# arm-debugger.net
KiCad netlist of a schematic drawn in Altium Designer
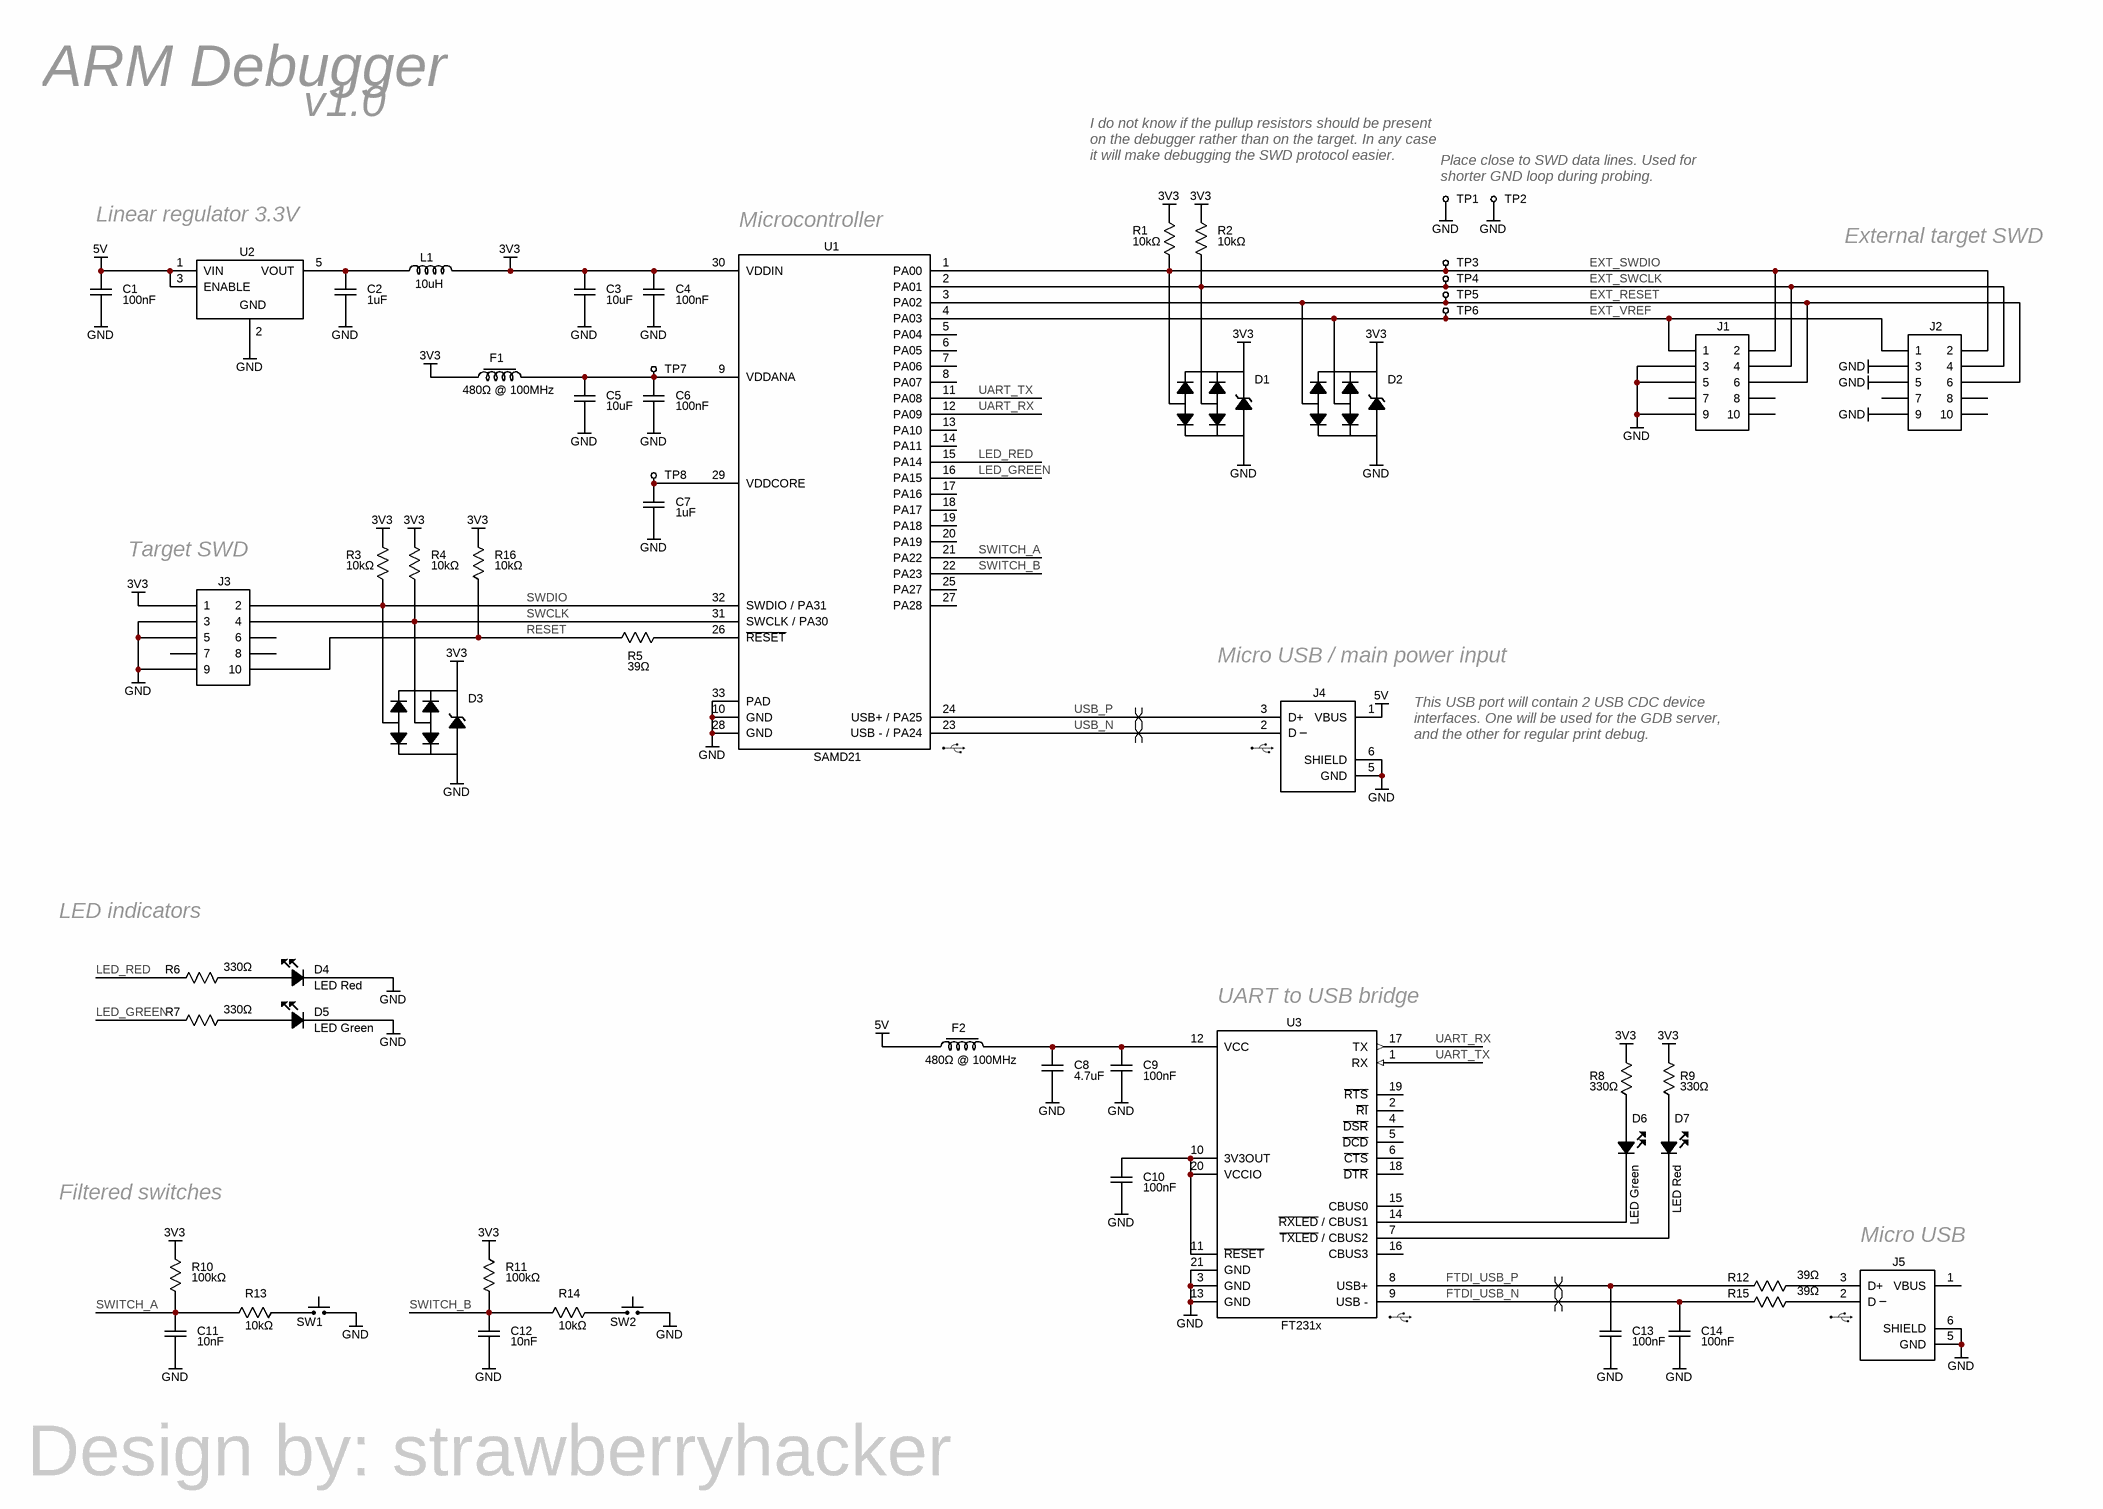
[diagram p0: arm-debugger.SchDoc]

(export (version "E")
  (design (tool "Eeschema 10.0.6"))
  (components
    (comp (ref "C1")
      (value "100nF")
      (footprint "capacitor 0603")
      (description "Capacitor 0603")
      (fields (field (name "Comment") "passive_5"))
      (libsource (lib "passive") (part "passive_5"))
    )
    (comp (ref "C2")
      (value "1uF")
      (footprint "capacitor 0603")
      (description "Capacitor 0603")
      (fields (field (name "Comment") "passive_5"))
      (libsource (lib "passive") (part "passive_5"))
    )
    (comp (ref "C3")
      (value "10uF")
      (footprint "capacitor 0603")
      (description "Capacitor 0603")
      (fields (field (name "Comment") "passive_5"))
      (libsource (lib "passive") (part "passive_5"))
    )
    (comp (ref "C4")
      (value "100nF")
      (footprint "capacitor 0603")
      (description "Capacitor 0603")
      (fields (field (name "Comment") "passive_5"))
      (libsource (lib "passive") (part "passive_5"))
    )
    (comp (ref "C5")
      (value "10uF")
      (footprint "capacitor 0603")
      (description "Capacitor 0603")
      (fields (field (name "Comment") "passive_5"))
      (libsource (lib "passive") (part "passive_5"))
    )
    (comp (ref "C6")
      (value "100nF")
      (footprint "capacitor 0603")
      (description "Capacitor 0603")
      (fields (field (name "Comment") "passive_5"))
      (libsource (lib "passive") (part "passive_5"))
    )
    (comp (ref "C7")
      (value "1uF")
      (footprint "capacitor 0603")
      (description "Capacitor 0603")
      (fields (field (name "Comment") "passive_5"))
      (libsource (lib "passive") (part "passive_5"))
    )
    (comp (ref "C8")
      (value "4.7uF")
      (footprint "capacitor 0603")
      (description "Capacitor 0603")
      (fields (field (name "Comment") "passive_5"))
      (libsource (lib "passive") (part "passive_5"))
    )
    (comp (ref "C9")
      (value "100nF")
      (footprint "capacitor 0603")
      (description "Capacitor 0603")
      (fields (field (name "Comment") "passive_5"))
      (libsource (lib "passive") (part "passive_5"))
    )
    (comp (ref "C10")
      (value "100nF")
      (footprint "capacitor 0603")
      (description "Capacitor 0603")
      (fields (field (name "Comment") "passive_5"))
      (libsource (lib "passive") (part "passive_5"))
    )
    (comp (ref "C11")
      (value "10nF")
      (footprint "capacitor 0603")
      (description "Capacitor 0603")
      (fields (field (name "Comment") "passive_5"))
      (libsource (lib "passive") (part "passive_5"))
    )
    (comp (ref "C12")
      (value "10nF")
      (footprint "capacitor 0603")
      (description "Capacitor 0603")
      (fields (field (name "Comment") "passive_5"))
      (libsource (lib "passive") (part "passive_5"))
    )
    (comp (ref "C13")
      (value "100nF")
      (footprint "capacitor 0603")
      (description "Capacitor 0603")
      (fields (field (name "Comment") "passive_5"))
      (libsource (lib "passive") (part "passive_5"))
    )
    (comp (ref "C14")
      (value "100nF")
      (footprint "capacitor 0603")
      (description "Capacitor 0603")
      (fields (field (name "Comment") "passive_5"))
      (libsource (lib "passive") (part "passive_5"))
    )
    (comp (ref "D1")
      (value "diode_3")
      (footprint "CM1293A-02SR")
      (description "TVS, 2 channels, standoff 3.3V,  diode array with avalanche diode")
      (libsource (lib "diode") (part "diode_3"))
    )
    (comp (ref "D2")
      (value "diode_3")
      (footprint "CM1293A-02SR")
      (description "TVS, 2 channels, standoff 3.3V,  diode array with avalanche diode")
      (libsource (lib "diode") (part "diode_3"))
    )
    (comp (ref "D3")
      (value "diode_3")
      (footprint "CM1293A-02SR")
      (description "TVS, 2 channels, standoff 3.3V,  diode array with avalanche diode")
      (libsource (lib "diode") (part "diode_3"))
    )
    (comp (ref "D4")
      (value "LED Red")
      (footprint "LED 0603 red")
      (description "LED 0603 red")
      (libsource (lib "diode") (part "diode_0"))
    )
    (comp (ref "D5")
      (value "LED Green")
      (footprint "LED 0603 green")
      (description "LED 0603 green")
      (libsource (lib "diode") (part "diode_1"))
    )
    (comp (ref "D6")
      (value "LED Green")
      (footprint "LED 0603 green")
      (description "LED 0603 green")
      (libsource (lib "diode") (part "diode_1"))
    )
    (comp (ref "D7")
      (value "LED Red")
      (footprint "LED 0603 red")
      (description "LED 0603 red")
      (libsource (lib "diode") (part "diode_0"))
    )
    (comp (ref "F1")
      (value "480Ω @ 100MHz")
      (footprint "ferrit bead 0603")
      (description "Ferrite bead 0603")
      (fields (field (name "Comment") "passive_8"))
      (libsource (lib "passive") (part "passive_8"))
    )
    (comp (ref "F2")
      (value "480Ω @ 100MHz")
      (footprint "ferrit bead 0603")
      (description "Ferrite bead 0603")
      (fields (field (name "Comment") "passive_8"))
      (libsource (lib "passive") (part "passive_8"))
    )
    (comp (ref "J1")
      (value "Header 1.27mm")
      (footprint "header male 2x5, pitch 1.27mm")
      (description "Header male 2x5, pitch 1.27mm")
      (libsource (lib "connector") (part "connector_17"))
    )
    (comp (ref "J2")
      (value "Header 2.54mm")
      (footprint "header male 2x5, pitch 2.54mm")
      (description "Header male 2x5, pitch 2.54mm")
      (libsource (lib "connector") (part "connector_30"))
    )
    (comp (ref "J3")
      (value "Header 1.27mm")
      (footprint "header male 2x5, pitch 1.27mm")
      (description "Header male 2x5, pitch 1.27mm")
      (libsource (lib "connector") (part "connector_17"))
    )
    (comp (ref "J4")
      (value "USB micro B")
      (footprint "USB mico B female")
      (libsource (lib "connector") (part "connector_34"))
    )
    (comp (ref "J5")
      (value "USB micro B")
      (footprint "USB mico B female")
      (libsource (lib "connector") (part "connector_34"))
    )
    (comp (ref "L1")
      (value "10uH")
      (footprint "inductor 0603")
      (description "Inductor 0603")
      (fields (field (name "Comment") "passive_9"))
      (libsource (lib "passive") (part "passive_9"))
    )
    (comp (ref "R1")
      (value "10kΩ")
      (footprint "resistor 0603")
      (description "Resistor 0603")
      (fields (field (name "Comment") "passive_2"))
      (libsource (lib "passive") (part "passive_2"))
    )
    (comp (ref "R2")
      (value "10kΩ")
      (footprint "resistor 0603")
      (description "Resistor 0603")
      (fields (field (name "Comment") "passive_2"))
      (libsource (lib "passive") (part "passive_2"))
    )
    (comp (ref "R3")
      (value "10kΩ")
      (footprint "resistor 0603")
      (description "Resistor 0603")
      (fields (field (name "Comment") "passive_2"))
      (libsource (lib "passive") (part "passive_2"))
    )
    (comp (ref "R4")
      (value "10kΩ")
      (footprint "resistor 0603")
      (description "Resistor 0603")
      (fields (field (name "Comment") "passive_2"))
      (libsource (lib "passive") (part "passive_2"))
    )
    (comp (ref "R5")
      (value "39Ω")
      (footprint "resistor 0603")
      (description "Resistor 0603")
      (fields (field (name "Comment") "passive_2"))
      (libsource (lib "passive") (part "passive_2"))
    )
    (comp (ref "R6")
      (value "330Ω")
      (footprint "resistor 0603")
      (description "Resistor 0603")
      (fields (field (name "Comment") "passive_2"))
      (libsource (lib "passive") (part "passive_2"))
    )
    (comp (ref "R7")
      (value "330Ω")
      (footprint "resistor 0603")
      (description "Resistor 0603")
      (fields (field (name "Comment") "passive_2"))
      (libsource (lib "passive") (part "passive_2"))
    )
    (comp (ref "R8")
      (value "330Ω")
      (footprint "resistor 0603")
      (description "Resistor 0603")
      (fields (field (name "Comment") "passive_2"))
      (libsource (lib "passive") (part "passive_2"))
    )
    (comp (ref "R9")
      (value "330Ω")
      (footprint "resistor 0603")
      (description "Resistor 0603")
      (fields (field (name "Comment") "passive_2"))
      (libsource (lib "passive") (part "passive_2"))
    )
    (comp (ref "R10")
      (value "100kΩ")
      (footprint "resistor 0603")
      (description "Resistor 0603")
      (fields (field (name "Comment") "passive_2"))
      (libsource (lib "passive") (part "passive_2"))
    )
    (comp (ref "R11")
      (value "100kΩ")
      (footprint "resistor 0603")
      (description "Resistor 0603")
      (fields (field (name "Comment") "passive_2"))
      (libsource (lib "passive") (part "passive_2"))
    )
    (comp (ref "R12")
      (value "39Ω")
      (footprint "resistor 0603")
      (description "Resistor 0603")
      (fields (field (name "Comment") "passive_2"))
      (libsource (lib "passive") (part "passive_2"))
    )
    (comp (ref "R13")
      (value "10kΩ")
      (footprint "resistor 0603")
      (description "Resistor 0603")
      (fields (field (name "Comment") "passive_2"))
      (libsource (lib "passive") (part "passive_2"))
    )
    (comp (ref "R14")
      (value "10kΩ")
      (footprint "resistor 0603")
      (description "Resistor 0603")
      (fields (field (name "Comment") "passive_2"))
      (libsource (lib "passive") (part "passive_2"))
    )
    (comp (ref "R15")
      (value "39Ω")
      (footprint "resistor 0603")
      (description "Resistor 0603")
      (fields (field (name "Comment") "passive_2"))
      (libsource (lib "passive") (part "passive_2"))
    )
    (comp (ref "R16")
      (value "10kΩ")
      (footprint "resistor 0603")
      (description "Resistor 0603")
      (fields (field (name "Comment") "passive_2"))
      (libsource (lib "passive") (part "passive_2"))
    )
    (comp (ref "SW1")
      (value "connector_35")
      (footprint "KMR621NG LFS")
      (description "Tactile switch SMD, tiny")
      (libsource (lib "sensor") (part "connector_35"))
    )
    (comp (ref "SW2")
      (value "connector_35")
      (footprint "KMR621NG LFS")
      (description "Tactile switch SMD, tiny")
      (libsource (lib "sensor") (part "connector_35"))
    )
    (comp (ref "TP1")
      (value "misc_2")
      (footprint "testpoint round, diameter 1mm")
      (description "Test-point round, diameter 1.0mm")
      (libsource (lib "miscellaneous") (part "misc_2"))
    )
    (comp (ref "TP2")
      (value "misc_2")
      (footprint "testpoint round, diameter 1mm")
      (description "Test-point round, diameter 1.0mm")
      (libsource (lib "miscellaneous") (part "misc_2"))
    )
    (comp (ref "TP3")
      (value "misc_2")
      (footprint "testpoint round, diameter 1mm")
      (description "Test-point round, diameter 1.0mm")
      (libsource (lib "miscellaneous") (part "misc_2"))
    )
    (comp (ref "TP4")
      (value "misc_2")
      (footprint "testpoint round, diameter 1mm")
      (description "Test-point round, diameter 1.0mm")
      (libsource (lib "miscellaneous") (part "misc_2"))
    )
    (comp (ref "TP5")
      (value "misc_2")
      (footprint "testpoint round, diameter 1mm")
      (description "Test-point round, diameter 1.0mm")
      (libsource (lib "miscellaneous") (part "misc_2"))
    )
    (comp (ref "TP6")
      (value "misc_2")
      (footprint "testpoint round, diameter 1mm")
      (description "Test-point round, diameter 1.0mm")
      (libsource (lib "miscellaneous") (part "misc_2"))
    )
    (comp (ref "TP7")
      (value "misc_2")
      (footprint "testpoint round, diameter 1mm")
      (description "Test-point round, diameter 1.0mm")
      (libsource (lib "miscellaneous") (part "misc_2"))
    )
    (comp (ref "TP8")
      (value "misc_2")
      (footprint "testpoint round, diameter 1mm")
      (description "Test-point round, diameter 1.0mm")
      (libsource (lib "miscellaneous") (part "misc_2"))
    )
    (comp (ref "U1")
      (value "SAMD21")
      (footprint "ATSAMD21E17D-MUT")
      (description "SAMD21, 48 MHz, 128KB flash, 16KB RAM, 32 pins, USB device")
      (libsource (lib "cpu") (part "cpu_0"))
    )
    (comp (ref "U2")
      (value "regulator_1")
      (footprint "TCR2EF33,LM(CT")
      (description "LDO fixed, 3.3V output, 0.2V dropout, 200mA")
      (libsource (lib "voltage-regulator") (part "regulator_1"))
    )
    (comp (ref "U3")
      (value "FT231x")
      (footprint "FT231XQ-R")
      (description "USB to UART converter, FTDI, single")
      (libsource (lib "integrated-circuit") (part "ic_1"))
    )
  )
  (nets
    (net (code "1") (name "/EXT_RESET") (class "Default")
      (node (ref "D2") (pin "2") (pintype "passive"))
      (node (ref "J1") (pin "6") (pinfunction "6_6") (pintype "passive"))
      (node (ref "J2") (pin "6") (pinfunction "6_6") (pintype "passive"))
      (node (ref "TP5") (pin "1") (pintype "passive"))
      (node (ref "U1") (pin "3") (pinfunction "PA02_3") (pintype "passive"))
    )
    (net (code "2") (name "/EXT_SWCLK") (class "Default")
      (node (ref "D1") (pin "3") (pintype "passive"))
      (node (ref "J1") (pin "4") (pinfunction "4_4") (pintype "passive"))
      (node (ref "J2") (pin "4") (pinfunction "4_4") (pintype "passive"))
      (node (ref "R2") (pin "1") (pintype "passive"))
      (node (ref "TP4") (pin "1") (pintype "passive"))
      (node (ref "U1") (pin "2") (pinfunction "PA01_2") (pintype "passive"))
    )
    (net (code "3") (name "/EXT_SWDIO") (class "Default")
      (node (ref "D1") (pin "2") (pintype "passive"))
      (node (ref "J1") (pin "2") (pinfunction "2_2") (pintype "passive"))
      (node (ref "J2") (pin "2") (pinfunction "2_2") (pintype "passive"))
      (node (ref "R1") (pin "1") (pintype "passive"))
      (node (ref "TP3") (pin "1") (pintype "passive"))
      (node (ref "U1") (pin "1") (pinfunction "PA00_1") (pintype "passive"))
    )
    (net (code "4") (name "/EXT_VREF") (class "Default")
      (node (ref "D2") (pin "3") (pintype "passive"))
      (node (ref "J1") (pin "1") (pinfunction "1_1") (pintype "passive"))
      (node (ref "J2") (pin "1") (pinfunction "1_1") (pintype "passive"))
      (node (ref "TP6") (pin "1") (pintype "passive"))
      (node (ref "U1") (pin "4") (pinfunction "PA03_4") (pintype "passive"))
    )
    (net (code "5") (name "/FTDI_USB_N") (class "Default")
      (node (ref "C14") (pin "2") (pinfunction "2_2") (pintype "passive"))
      (node (ref "R15") (pin "2") (pinfunction "2_2") (pintype "passive"))
      (node (ref "U3") (pin "9") (pinfunction "USB_-_9") (pintype "passive"))
    )
    (net (code "6") (name "/FTDI_USB_P") (class "Default")
      (node (ref "C13") (pin "2") (pinfunction "2_2") (pintype "passive"))
      (node (ref "R12") (pin "2") (pinfunction "2_2") (pintype "passive"))
      (node (ref "U3") (pin "8") (pinfunction "USB+_8") (pintype "passive"))
    )
    (net (code "7") (name "/LED_GREEN") (class "Default")
      (node (ref "R7") (pin "2") (pinfunction "2_2") (pintype "passive"))
      (node (ref "U1") (pin "16") (pinfunction "PA15_16") (pintype "passive"))
    )
    (net (code "8") (name "/LED_RED") (class "Default")
      (node (ref "R6") (pin "2") (pinfunction "2_2") (pintype "passive"))
      (node (ref "U1") (pin "15") (pinfunction "PA14_15") (pintype "passive"))
    )
    (net (code "9") (name "/RESET") (class "Default")
      (node (ref "J3") (pin "10") (pinfunction "10_10") (pintype "passive"))
      (node (ref "R16") (pin "1") (pintype "passive"))
      (node (ref "R5") (pin "2") (pinfunction "2_2") (pintype "passive"))
    )
    (net (code "10") (name "/SWCLK") (class "Default")
      (node (ref "D3") (pin "3") (pintype "passive"))
      (node (ref "J3") (pin "4") (pinfunction "4_4") (pintype "passive"))
      (node (ref "R4") (pin "1") (pintype "passive"))
      (node (ref "U1") (pin "31") (pinfunction "SWCLK_/_PA30_31") (pintype "passive"))
    )
    (net (code "11") (name "/SWDIO") (class "Default")
      (node (ref "D3") (pin "2") (pintype "passive"))
      (node (ref "J3") (pin "2") (pinfunction "2_2") (pintype "passive"))
      (node (ref "R3") (pin "1") (pintype "passive"))
      (node (ref "U1") (pin "32") (pinfunction "SWDIO_/_PA31_32") (pintype "passive"))
    )
    (net (code "12") (name "/SWITCH_A") (class "Default")
      (node (ref "C11") (pin "2") (pinfunction "2_2") (pintype "passive"))
      (node (ref "R10") (pin "1") (pintype "passive"))
      (node (ref "R13") (pin "2") (pinfunction "2_2") (pintype "passive"))
      (node (ref "U1") (pin "21") (pinfunction "PA22_21") (pintype "passive"))
    )
    (net (code "13") (name "/SWITCH_B") (class "Default")
      (node (ref "C12") (pin "2") (pinfunction "2_2") (pintype "passive"))
      (node (ref "R11") (pin "1") (pintype "passive"))
      (node (ref "R14") (pin "2") (pinfunction "2_2") (pintype "passive"))
      (node (ref "U1") (pin "22") (pinfunction "PA23_22") (pintype "passive"))
    )
    (net (code "14") (name "/UART_RX") (class "Default")
      (node (ref "U1") (pin "12") (pinfunction "PA09_12") (pintype "passive"))
      (node (ref "U3") (pin "17") (pinfunction "TX_17") (pintype "output"))
    )
    (net (code "15") (name "/UART_TX") (class "Default")
      (node (ref "U1") (pin "11") (pinfunction "PA08_11") (pintype "passive"))
      (node (ref "U3") (pin "1") (pinfunction "RX_1") (pintype "input"))
    )
    (net (code "16") (name "/USB_N") (class "Default")
      (node (ref "J4") (pin "2") (pinfunction "D_2") (pintype "passive"))
      (node (ref "U1") (pin "23") (pinfunction "USB_-_/_PA24_23") (pintype "passive"))
    )
    (net (code "17") (name "/USB_P") (class "Default")
      (node (ref "J4") (pin "3") (pinfunction "D+_3") (pintype "passive"))
      (node (ref "U1") (pin "24") (pinfunction "USB+_/_PA25_24") (pintype "passive"))
    )
    (net (code "18") (name "3V3") (class "Default")
      (node (ref "C3") (pin "2") (pinfunction "2_2") (pintype "passive"))
      (node (ref "C4") (pin "2") (pinfunction "2_2") (pintype "passive"))
      (node (ref "D1") (pin "4") (pintype "passive"))
      (node (ref "D2") (pin "4") (pintype "passive"))
      (node (ref "D3") (pin "4") (pintype "passive"))
      (node (ref "F1") (pin "1") (pintype "passive"))
      (node (ref "J3") (pin "1") (pinfunction "1_1") (pintype "passive"))
      (node (ref "L1") (pin "2") (pinfunction "2_2") (pintype "passive"))
      (node (ref "R1") (pin "2") (pinfunction "2_2") (pintype "passive"))
      (node (ref "R10") (pin "2") (pinfunction "2_2") (pintype "passive"))
      (node (ref "R11") (pin "2") (pinfunction "2_2") (pintype "passive"))
      (node (ref "R16") (pin "2") (pinfunction "2_2") (pintype "passive"))
      (node (ref "R2") (pin "2") (pinfunction "2_2") (pintype "passive"))
      (node (ref "R3") (pin "2") (pinfunction "2_2") (pintype "passive"))
      (node (ref "R4") (pin "2") (pinfunction "2_2") (pintype "passive"))
      (node (ref "R8") (pin "2") (pinfunction "2_2") (pintype "passive"))
      (node (ref "R9") (pin "2") (pinfunction "2_2") (pintype "passive"))
      (node (ref "U1") (pin "30") (pinfunction "VDDIN_30") (pintype "passive"))
    )
    (net (code "19") (name "5V") (class "Default")
      (node (ref "C1") (pin "2") (pinfunction "2_2") (pintype "passive"))
      (node (ref "F2") (pin "1") (pintype "passive"))
      (node (ref "J4") (pin "1") (pinfunction "VBUS_1") (pintype "passive"))
      (node (ref "U2") (pin "1") (pinfunction "VIN_1") (pintype "passive"))
      (node (ref "U2") (pin "3") (pinfunction "ENABLE_3") (pintype "passive"))
    )
    (net (code "20") (name "GND") (class "Default")
      (node (ref "C1") (pin "1") (pinfunction "1_1") (pintype "passive"))
      (node (ref "C10") (pin "1") (pinfunction "1_1") (pintype "passive"))
      (node (ref "C11") (pin "1") (pinfunction "1_1") (pintype "passive"))
      (node (ref "C12") (pin "1") (pinfunction "1_1") (pintype "passive"))
      (node (ref "C13") (pin "1") (pinfunction "1_1") (pintype "passive"))
      (node (ref "C14") (pin "1") (pinfunction "1_1") (pintype "passive"))
      (node (ref "C2") (pin "1") (pinfunction "1_1") (pintype "passive"))
      (node (ref "C3") (pin "1") (pinfunction "1_1") (pintype "passive"))
      (node (ref "C4") (pin "1") (pinfunction "1_1") (pintype "passive"))
      (node (ref "C5") (pin "1") (pinfunction "1_1") (pintype "passive"))
      (node (ref "C6") (pin "1") (pinfunction "1_1") (pintype "passive"))
      (node (ref "C7") (pin "1") (pinfunction "1_1") (pintype "passive"))
      (node (ref "C8") (pin "1") (pinfunction "1_1") (pintype "passive"))
      (node (ref "C9") (pin "1") (pinfunction "1_1") (pintype "passive"))
      (node (ref "D1") (pin "1") (pintype "passive"))
      (node (ref "D2") (pin "1") (pintype "passive"))
      (node (ref "D3") (pin "1") (pintype "passive"))
      (node (ref "D4") (pin "2") (pinfunction "2_2") (pintype "passive"))
      (node (ref "D5") (pin "2") (pinfunction "2_2") (pintype "passive"))
      (node (ref "J1") (pin "3") (pinfunction "3_3") (pintype "passive"))
      (node (ref "J1") (pin "5") (pinfunction "5_5") (pintype "passive"))
      (node (ref "J1") (pin "9") (pinfunction "9_9") (pintype "passive"))
      (node (ref "J2") (pin "3") (pinfunction "3_3") (pintype "passive"))
      (node (ref "J2") (pin "5") (pinfunction "5_5") (pintype "passive"))
      (node (ref "J2") (pin "9") (pinfunction "9_9") (pintype "passive"))
      (node (ref "J3") (pin "3") (pinfunction "3_3") (pintype "passive"))
      (node (ref "J3") (pin "5") (pinfunction "5_5") (pintype "passive"))
      (node (ref "J3") (pin "9") (pinfunction "9_9") (pintype "passive"))
      (node (ref "J4") (pin "5") (pinfunction "GND_5") (pintype "passive"))
      (node (ref "J4") (pin "6") (pinfunction "SHIELD_6") (pintype "passive"))
      (node (ref "J5") (pin "5") (pinfunction "GND_5") (pintype "passive"))
      (node (ref "J5") (pin "6") (pinfunction "SHIELD_6") (pintype "passive"))
      (node (ref "SW1") (pin "2") (pintype "passive"))
      (node (ref "SW2") (pin "2") (pintype "passive"))
      (node (ref "TP1") (pin "1") (pintype "passive"))
      (node (ref "TP2") (pin "1") (pintype "passive"))
      (node (ref "U1") (pin "10") (pinfunction "GND_10") (pintype "passive"))
      (node (ref "U1") (pin "28") (pinfunction "GND_28") (pintype "passive"))
      (node (ref "U1") (pin "33") (pinfunction "PAD_33") (pintype "passive"))
      (node (ref "U2") (pin "2") (pintype "passive"))
      (node (ref "U3") (pin "13") (pinfunction "GND_13") (pintype "passive"))
      (node (ref "U3") (pin "21") (pinfunction "GND_21") (pintype "passive"))
      (node (ref "U3") (pin "3") (pinfunction "GND_3") (pintype "passive"))
    )
    (net (code "21") (name "Net-(D4-Pad1)") (class "Default")
      (node (ref "D4") (pin "1") (pinfunction "1_1") (pintype "passive"))
      (node (ref "R6") (pin "1") (pintype "passive"))
    )
    (net (code "22") (name "Net-(D5-Pad1)") (class "Default")
      (node (ref "D5") (pin "1") (pinfunction "1_1") (pintype "passive"))
      (node (ref "R7") (pin "1") (pintype "passive"))
    )
    (net (code "23") (name "Net-(D6-Pad1)") (class "Default")
      (node (ref "D6") (pin "1") (pinfunction "1_1") (pintype "passive"))
      (node (ref "R8") (pin "1") (pintype "passive"))
    )
    (net (code "24") (name "Net-(D7-Pad1)") (class "Default")
      (node (ref "D7") (pin "1") (pinfunction "1_1") (pintype "passive"))
      (node (ref "R9") (pin "1") (pintype "passive"))
    )
    (net (code "25") (name "Net-(J5-D)") (class "Default")
      (node (ref "J5") (pin "2") (pinfunction "D_2") (pintype "passive"))
      (node (ref "R15") (pin "1") (pintype "passive"))
    )
    (net (code "26") (name "Net-(J5-D+)") (class "Default")
      (node (ref "J5") (pin "3") (pinfunction "D+_3") (pintype "passive"))
      (node (ref "R12") (pin "1") (pintype "passive"))
    )
    (net (code "27") (name "Net-(R13-Pad1)") (class "Default")
      (node (ref "R13") (pin "1") (pintype "passive"))
      (node (ref "SW1") (pin "1") (pintype "passive"))
    )
    (net (code "28") (name "Net-(R14-Pad1)") (class "Default")
      (node (ref "R14") (pin "1") (pintype "passive"))
      (node (ref "SW2") (pin "1") (pintype "passive"))
    )
    (net (code "29") (name "Net-(U1-VDDANA)") (class "Default")
      (node (ref "C5") (pin "2") (pinfunction "2_2") (pintype "passive"))
      (node (ref "C6") (pin "2") (pinfunction "2_2") (pintype "passive"))
      (node (ref "F1") (pin "2") (pinfunction "2_2") (pintype "passive"))
      (node (ref "TP7") (pin "1") (pintype "passive"))
      (node (ref "U1") (pin "9") (pinfunction "VDDANA_9") (pintype "passive"))
    )
    (net (code "30") (name "Net-(U1-VDDCORE)") (class "Default")
      (node (ref "C7") (pin "2") (pinfunction "2_2") (pintype "passive"))
      (node (ref "TP8") (pin "1") (pintype "passive"))
      (node (ref "U1") (pin "29") (pinfunction "VDDCORE_29") (pintype "passive"))
    )
    (net (code "31") (name "Net-(U1-~{RESET})") (class "Default")
      (node (ref "R5") (pin "1") (pintype "passive"))
      (node (ref "U1") (pin "26") (pinfunction "~{RESET}_26") (pintype "passive"))
    )
    (net (code "32") (name "Net-(U2-VOUT)") (class "Default")
      (node (ref "C2") (pin "2") (pinfunction "2_2") (pintype "passive"))
      (node (ref "L1") (pin "1") (pintype "passive"))
      (node (ref "U2") (pin "5") (pinfunction "VOUT_5") (pintype "passive"))
    )
    (net (code "33") (name "Net-(U3-3V3OUT)") (class "Default")
      (node (ref "C10") (pin "2") (pinfunction "2_2") (pintype "passive"))
      (node (ref "U3") (pin "10") (pinfunction "3V3OUT_10") (pintype "passive"))
      (node (ref "U3") (pin "11") (pinfunction "~{RESET}_11") (pintype "passive"))
      (node (ref "U3") (pin "20") (pinfunction "VCCIO_20") (pintype "passive"))
    )
    (net (code "34") (name "Net-(U3-VCC)") (class "Default")
      (node (ref "C8") (pin "2") (pinfunction "2_2") (pintype "passive"))
      (node (ref "C9") (pin "2") (pinfunction "2_2") (pintype "passive"))
      (node (ref "F2") (pin "2") (pinfunction "2_2") (pintype "passive"))
      (node (ref "U3") (pin "12") (pinfunction "VCC_12") (pintype "passive"))
    )
    (net (code "35") (name "Net-(U3-~{RXLED}_{slash}_CBUS1)") (class "Default")
      (node (ref "D6") (pin "2") (pinfunction "2_2") (pintype "passive"))
      (node (ref "U3") (pin "14") (pinfunction "~{RXLED}_/_CBUS1_14") (pintype "passive"))
    )
    (net (code "36") (name "Net-(U3-~{TXLED}_{slash}_CBUS2)") (class "Default")
      (node (ref "D7") (pin "2") (pinfunction "2_2") (pintype "passive"))
      (node (ref "U3") (pin "7") (pinfunction "~{TXLED}_/_CBUS2_7") (pintype "passive"))
    )
    (net (code "37") (name "unconnected-(J1-Pad7)") (class "Default")
      (node (ref "J1") (pin "7") (pinfunction "7_7") (pintype "passive"))
    )
    (net (code "38") (name "unconnected-(J1-Pad8)") (class "Default")
      (node (ref "J1") (pin "8") (pinfunction "8_8") (pintype "passive"))
    )
    (net (code "39") (name "unconnected-(J1-Pad10)") (class "Default")
      (node (ref "J1") (pin "10") (pinfunction "10_10") (pintype "passive"))
    )
    (net (code "40") (name "unconnected-(J2-Pad7)") (class "Default")
      (node (ref "J2") (pin "7") (pinfunction "7_7") (pintype "passive"))
    )
    (net (code "41") (name "unconnected-(J2-Pad8)") (class "Default")
      (node (ref "J2") (pin "8") (pinfunction "8_8") (pintype "passive"))
    )
    (net (code "42") (name "unconnected-(J2-Pad10)") (class "Default")
      (node (ref "J2") (pin "10") (pinfunction "10_10") (pintype "passive"))
    )
    (net (code "43") (name "unconnected-(J3-Pad6)") (class "Default")
      (node (ref "J3") (pin "6") (pinfunction "6_6") (pintype "passive"))
    )
    (net (code "44") (name "unconnected-(J3-Pad7)") (class "Default")
      (node (ref "J3") (pin "7") (pinfunction "7_7") (pintype "passive"))
    )
    (net (code "45") (name "unconnected-(J3-Pad8)") (class "Default")
      (node (ref "J3") (pin "8") (pinfunction "8_8") (pintype "passive"))
    )
    (net (code "46") (name "unconnected-(J5-VBUS-Pad1)") (class "Default")
      (node (ref "J5") (pin "1") (pinfunction "VBUS_1") (pintype "passive"))
    )
    (net (code "47") (name "unconnected-(U1-PA04-Pad5)") (class "Default")
      (node (ref "U1") (pin "5") (pinfunction "PA04_5") (pintype "passive"))
    )
    (net (code "48") (name "unconnected-(U1-PA05-Pad6)") (class "Default")
      (node (ref "U1") (pin "6") (pinfunction "PA05_6") (pintype "passive"))
    )
    (net (code "49") (name "unconnected-(U1-PA06-Pad7)") (class "Default")
      (node (ref "U1") (pin "7") (pinfunction "PA06_7") (pintype "passive"))
    )
    (net (code "50") (name "unconnected-(U1-PA07-Pad8)") (class "Default")
      (node (ref "U1") (pin "8") (pinfunction "PA07_8") (pintype "passive"))
    )
    (net (code "51") (name "unconnected-(U1-PA10-Pad13)") (class "Default")
      (node (ref "U1") (pin "13") (pinfunction "PA10_13") (pintype "passive"))
    )
    (net (code "52") (name "unconnected-(U1-PA11-Pad14)") (class "Default")
      (node (ref "U1") (pin "14") (pinfunction "PA11_14") (pintype "passive"))
    )
    (net (code "53") (name "unconnected-(U1-PA16-Pad17)") (class "Default")
      (node (ref "U1") (pin "17") (pinfunction "PA16_17") (pintype "passive"))
    )
    (net (code "54") (name "unconnected-(U1-PA17-Pad18)") (class "Default")
      (node (ref "U1") (pin "18") (pinfunction "PA17_18") (pintype "passive"))
    )
    (net (code "55") (name "unconnected-(U1-PA18-Pad19)") (class "Default")
      (node (ref "U1") (pin "19") (pinfunction "PA18_19") (pintype "passive"))
    )
    (net (code "56") (name "unconnected-(U1-PA19-Pad20)") (class "Default")
      (node (ref "U1") (pin "20") (pinfunction "PA19_20") (pintype "passive"))
    )
    (net (code "57") (name "unconnected-(U1-PA27-Pad25)") (class "Default")
      (node (ref "U1") (pin "25") (pinfunction "PA27_25") (pintype "passive"))
    )
    (net (code "58") (name "unconnected-(U1-PA28-Pad27)") (class "Default")
      (node (ref "U1") (pin "27") (pinfunction "PA28_27") (pintype "passive"))
    )
    (net (code "59") (name "unconnected-(U3-CBUS0-Pad15)") (class "Default")
      (node (ref "U3") (pin "15") (pinfunction "CBUS0_15") (pintype "passive"))
    )
    (net (code "60") (name "unconnected-(U3-CBUS3-Pad16)") (class "Default")
      (node (ref "U3") (pin "16") (pinfunction "CBUS3_16") (pintype "passive"))
    )
    (net (code "61") (name "unconnected-(U3-~{CTS}-Pad6)") (class "Default")
      (node (ref "U3") (pin "6") (pinfunction "~{CTS}_6") (pintype "passive"))
    )
    (net (code "62") (name "unconnected-(U3-~{DCD}-Pad5)") (class "Default")
      (node (ref "U3") (pin "5") (pinfunction "~{DCD}_5") (pintype "passive"))
    )
    (net (code "63") (name "unconnected-(U3-~{DSR}-Pad4)") (class "Default")
      (node (ref "U3") (pin "4") (pinfunction "~{DSR}_4") (pintype "passive"))
    )
    (net (code "64") (name "unconnected-(U3-~{DTR}-Pad18)") (class "Default")
      (node (ref "U3") (pin "18") (pinfunction "~{DTR}_18") (pintype "passive"))
    )
    (net (code "65") (name "unconnected-(U3-~{RI}-Pad2)") (class "Default")
      (node (ref "U3") (pin "2") (pinfunction "~{RI}_2") (pintype "passive"))
    )
    (net (code "66") (name "unconnected-(U3-~{RTS}-Pad19)") (class "Default")
      (node (ref "U3") (pin "19") (pinfunction "~{RTS}_19") (pintype "passive"))
    )
  )
)
